# ATXBreakout.net
KiCad netlist of a schematic drawn in EAGLE
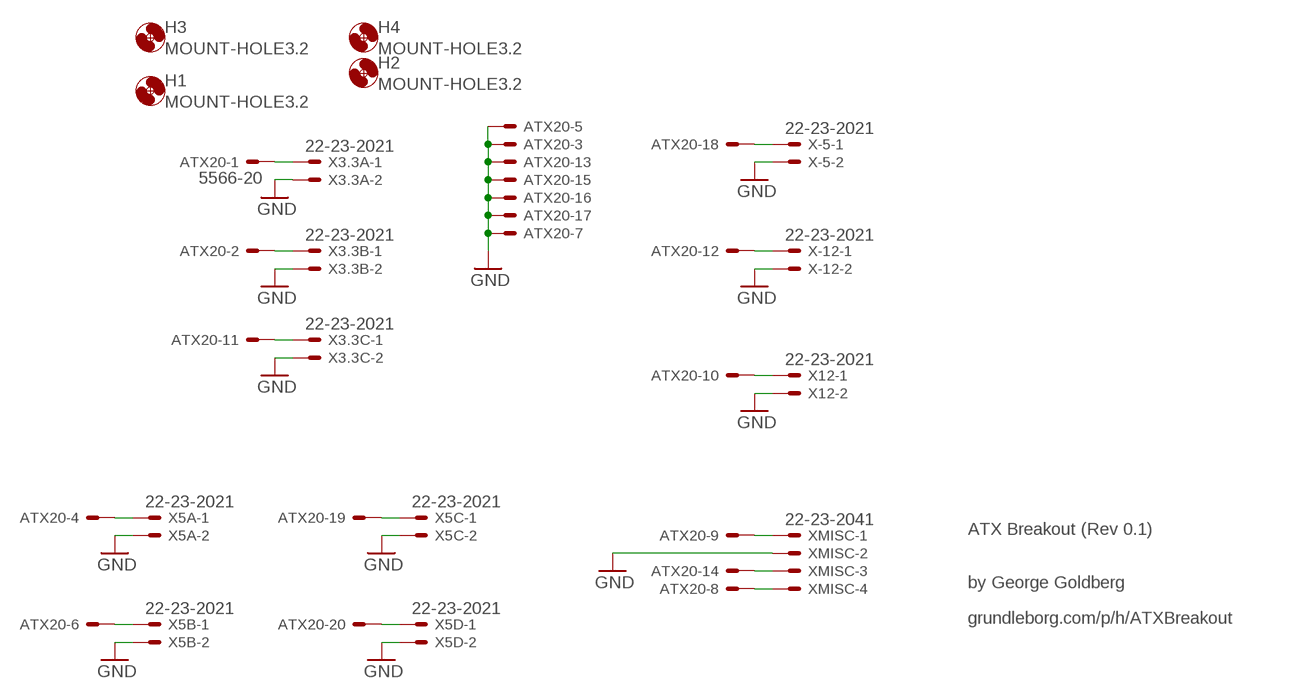
[diagram p0: schematic, sheet 1]

(export (version "E")
  (design (tool "Eeschema 10.0.6"))
  (components
    (comp (ref "ATX20")
      (value "5566-20")
      (footprint "eagle-import:5566-20")
      (libsource (lib "eagle-import") (part "5566-20"))
    )
    (comp (ref "H1")
      (value "MOUNT-HOLE3.2")
      (footprint "eagle-import:3,2")
      (libsource (lib "eagle-import") (part "MOUNT-HOLE3.2"))
    )
    (comp (ref "H2")
      (value "MOUNT-HOLE3.2")
      (footprint "eagle-import:3,2")
      (libsource (lib "eagle-import") (part "MOUNT-HOLE3.2"))
    )
    (comp (ref "H3")
      (value "MOUNT-HOLE3.2")
      (footprint "eagle-import:3,2")
      (libsource (lib "eagle-import") (part "MOUNT-HOLE3.2"))
    )
    (comp (ref "H4")
      (value "MOUNT-HOLE3.2")
      (footprint "eagle-import:3,2")
      (libsource (lib "eagle-import") (part "MOUNT-HOLE3.2"))
    )
    (comp (ref "X-5")
      (value "22-23-2021")
      (footprint "eagle-import:22-23-2021")
      (fields (field (name "MF") "MOLEX"))
      (libsource (lib "eagle-import") (part "22-23-2021"))
    )
    (comp (ref "X-12")
      (value "22-23-2021")
      (footprint "eagle-import:22-23-2021")
      (fields (field (name "MF") "MOLEX"))
      (libsource (lib "eagle-import") (part "22-23-2021"))
    )
    (comp (ref "X3.3A")
      (value "22-23-2021")
      (footprint "eagle-import:22-23-2021")
      (fields (field (name "MF") "MOLEX"))
      (libsource (lib "eagle-import") (part "22-23-2021"))
    )
    (comp (ref "X3.3B")
      (value "22-23-2021")
      (footprint "eagle-import:22-23-2021")
      (fields (field (name "MF") "MOLEX"))
      (libsource (lib "eagle-import") (part "22-23-2021"))
    )
    (comp (ref "X3.3C")
      (value "22-23-2021")
      (footprint "eagle-import:22-23-2021")
      (fields (field (name "MF") "MOLEX"))
      (libsource (lib "eagle-import") (part "22-23-2021"))
    )
    (comp (ref "X5A")
      (value "22-23-2021")
      (footprint "eagle-import:22-23-2021")
      (fields (field (name "MF") "MOLEX"))
      (libsource (lib "eagle-import") (part "22-23-2021"))
    )
    (comp (ref "X5B")
      (value "22-23-2021")
      (footprint "eagle-import:22-23-2021")
      (fields (field (name "MF") "MOLEX"))
      (libsource (lib "eagle-import") (part "22-23-2021"))
    )
    (comp (ref "X5C")
      (value "22-23-2021")
      (footprint "eagle-import:22-23-2021")
      (fields (field (name "MF") "MOLEX"))
      (libsource (lib "eagle-import") (part "22-23-2021"))
    )
    (comp (ref "X5D")
      (value "22-23-2021")
      (footprint "eagle-import:22-23-2021")
      (fields (field (name "MF") "MOLEX"))
      (libsource (lib "eagle-import") (part "22-23-2021"))
    )
    (comp (ref "X12")
      (value "22-23-2021")
      (footprint "eagle-import:22-23-2021")
      (fields (field (name "MF") "MOLEX"))
      (libsource (lib "eagle-import") (part "22-23-2021"))
    )
    (comp (ref "XMISC")
      (value "22-23-2041")
      (footprint "eagle-import:22-23-2041")
      (fields (field (name "MF") "MOLEX"))
      (libsource (lib "eagle-import") (part "22-23-2041"))
    )
  )
  (nets
    (net (code "1") (name "GND") (class "Default")
      (node (ref "ATX20") (pin "13") (pinfunction "S_13") (pintype "passive"))
      (node (ref "ATX20") (pin "15") (pinfunction "S_15") (pintype "passive"))
      (node (ref "ATX20") (pin "16") (pinfunction "S_16") (pintype "passive"))
      (node (ref "ATX20") (pin "17") (pinfunction "S_17") (pintype "passive"))
      (node (ref "ATX20") (pin "3") (pinfunction "S_3") (pintype "passive"))
      (node (ref "ATX20") (pin "5") (pinfunction "S_5") (pintype "passive"))
      (node (ref "ATX20") (pin "7") (pinfunction "S_7") (pintype "passive"))
      (node (ref "X-12") (pin "2") (pinfunction "S_2") (pintype "passive"))
      (node (ref "X-5") (pin "2") (pinfunction "S_2") (pintype "passive"))
      (node (ref "X12") (pin "2") (pinfunction "S_2") (pintype "passive"))
      (node (ref "X3.3A") (pin "2") (pinfunction "S_2") (pintype "passive"))
      (node (ref "X3.3B") (pin "2") (pinfunction "S_2") (pintype "passive"))
      (node (ref "X3.3C") (pin "2") (pinfunction "S_2") (pintype "passive"))
      (node (ref "X5A") (pin "2") (pinfunction "S_2") (pintype "passive"))
      (node (ref "X5B") (pin "2") (pinfunction "S_2") (pintype "passive"))
      (node (ref "X5C") (pin "2") (pinfunction "S_2") (pintype "passive"))
      (node (ref "X5D") (pin "2") (pinfunction "S_2") (pintype "passive"))
      (node (ref "XMISC") (pin "2") (pinfunction "S_2") (pintype "passive"))
    )
    (net (code "2") (name "Net-(ATX20A-S)") (class "Default")
      (node (ref "ATX20") (pin "1") (pinfunction "S_1") (pintype "passive"))
      (node (ref "X3.3A") (pin "1") (pinfunction "S_1") (pintype "passive"))
    )
    (net (code "3") (name "Net-(ATX20B-S)") (class "Default")
      (node (ref "ATX20") (pin "10") (pinfunction "S_10") (pintype "passive"))
      (node (ref "X12") (pin "1") (pinfunction "S_1") (pintype "passive"))
    )
    (net (code "4") (name "Net-(ATX20C-S)") (class "Default")
      (node (ref "ATX20") (pin "11") (pinfunction "S_11") (pintype "passive"))
      (node (ref "X3.3C") (pin "1") (pinfunction "S_1") (pintype "passive"))
    )
    (net (code "5") (name "Net-(ATX20D-S)") (class "Default")
      (node (ref "ATX20") (pin "12") (pinfunction "S_12") (pintype "passive"))
      (node (ref "X-12") (pin "1") (pinfunction "S_1") (pintype "passive"))
    )
    (net (code "6") (name "Net-(ATX20F-S)") (class "Default")
      (node (ref "ATX20") (pin "14") (pinfunction "S_14") (pintype "passive"))
      (node (ref "XMISC") (pin "3") (pinfunction "S_3") (pintype "passive"))
    )
    (net (code "7") (name "Net-(ATX20J-S)") (class "Default")
      (node (ref "ATX20") (pin "18") (pinfunction "S_18") (pintype "passive"))
      (node (ref "X-5") (pin "1") (pinfunction "S_1") (pintype "passive"))
    )
    (net (code "8") (name "Net-(ATX20K-S)") (class "Default")
      (node (ref "ATX20") (pin "19") (pinfunction "S_19") (pintype "passive"))
      (node (ref "X5C") (pin "1") (pinfunction "S_1") (pintype "passive"))
    )
    (net (code "9") (name "Net-(ATX20L-S)") (class "Default")
      (node (ref "ATX20") (pin "2") (pinfunction "S_2") (pintype "passive"))
      (node (ref "X3.3B") (pin "1") (pinfunction "S_1") (pintype "passive"))
    )
    (net (code "10") (name "Net-(ATX20M-S)") (class "Default")
      (node (ref "ATX20") (pin "20") (pinfunction "S_20") (pintype "passive"))
      (node (ref "X5D") (pin "1") (pinfunction "S_1") (pintype "passive"))
    )
    (net (code "11") (name "Net-(ATX20O-S)") (class "Default")
      (node (ref "ATX20") (pin "4") (pinfunction "S_4") (pintype "passive"))
      (node (ref "X5A") (pin "1") (pinfunction "S_1") (pintype "passive"))
    )
    (net (code "12") (name "Net-(ATX20Q-S)") (class "Default")
      (node (ref "ATX20") (pin "6") (pinfunction "S_6") (pintype "passive"))
      (node (ref "X5B") (pin "1") (pinfunction "S_1") (pintype "passive"))
    )
    (net (code "13") (name "Net-(ATX20S-S)") (class "Default")
      (node (ref "ATX20") (pin "8") (pinfunction "S_8") (pintype "passive"))
      (node (ref "XMISC") (pin "4") (pinfunction "S_4") (pintype "passive"))
    )
    (net (code "14") (name "Net-(ATX20T-S)") (class "Default")
      (node (ref "ATX20") (pin "9") (pinfunction "S_9") (pintype "passive"))
      (node (ref "XMISC") (pin "1") (pinfunction "S_1") (pintype "passive"))
    )
  )
)
